# PowerMeasurement.net
KiCad netlist of a schematic drawn in Altium Designer
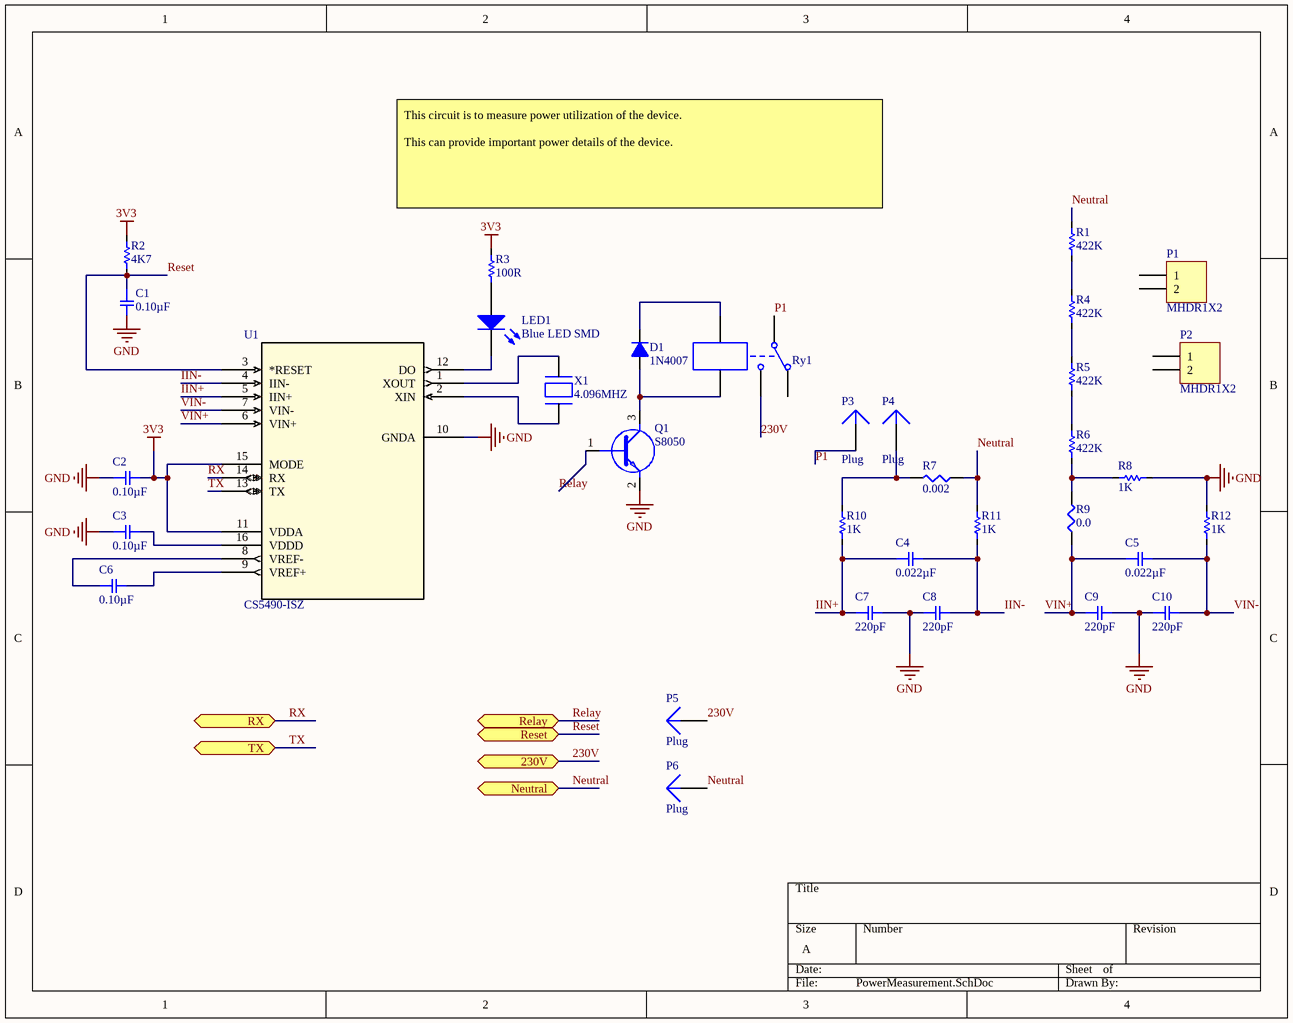
[diagram p0: PowerMeasurement.SchDoc]

(export (version "E")
  (design (tool "Eeschema 10.0.6"))
  (components
    (comp (ref "C1")
      (value "0.10µF")
      (footprint "SMD-0402C")
      (description "CAP CER 0.1UF 16V X7R 0402")
      (fields
        (field (name "DIGI-KEY PART NUMBER") "490-4759-1-ND")
        (field (name "PART NUMBER") "GCM155R71C104KA55D")
      )
      (libsource (lib "Capacitors") (part "GCM155R71C104KA55D"))
    )
    (comp (ref "C2")
      (value "0.10µF")
      (footprint "SMD-0402C")
      (description "CAP CER 0.1UF 16V X7R 0402")
      (fields
        (field (name "DIGI-KEY PART NUMBER") "490-4759-1-ND")
        (field (name "PART NUMBER") "GCM155R71C104KA55D")
      )
      (libsource (lib "Capacitors") (part "GCM155R71C104KA55D"))
    )
    (comp (ref "C3")
      (value "0.10µF")
      (footprint "SMD-0402C")
      (description "CAP CER 0.1UF 16V X7R 0402")
      (fields
        (field (name "DIGI-KEY PART NUMBER") "490-4759-1-ND")
        (field (name "PART NUMBER") "GCM155R71C104KA55D")
      )
      (libsource (lib "Capacitors") (part "GCM155R71C104KA55D"))
    )
    (comp (ref "C4")
      (value "0.022µF")
      (footprint "SMD-0402C")
      (description "CAP CER 0.022UF 50V X7R 0402")
      (fields
        (field (name "DIGI-KEY PART NUMBER") "490-4763-1-ND")
        (field (name "PART NUMBER") "GCM155R71H223KA55D")
      )
      (libsource (lib "Capacitors") (part "GCM155R71H223KA55D"))
    )
    (comp (ref "C5")
      (value "0.022µF")
      (footprint "SMD-0402C")
      (description "CAP CER 0.022UF 50V X7R 0402")
      (fields
        (field (name "DIGI-KEY PART NUMBER") "490-4763-1-ND")
        (field (name "PART NUMBER") "GCM155R71H223KA55D")
      )
      (libsource (lib "Capacitors") (part "GCM155R71H223KA55D"))
    )
    (comp (ref "C6")
      (value "0.10µF")
      (footprint "SMD-0402C")
      (description "CAP CER 0.1UF 16V X7R 0402")
      (fields
        (field (name "DIGI-KEY PART NUMBER") "490-4759-1-ND")
        (field (name "PART NUMBER") "GCM155R71C104KA55D")
      )
      (libsource (lib "Capacitors") (part "GCM155R71C104KA55D"))
    )
    (comp (ref "C7")
      (value "220pF")
      (footprint "SMD-0402C")
      (description "CAP CER 220PF 50V NP0 0402")
      (fields
        (field (name "DIGI-KEY PART NUMBER") "490-4927-1-ND")
        (field (name "PART NUMBER") "GCM1555C1H221JA16D")
      )
      (libsource (lib "Capacitors") (part "GCM1555C1H221JA16D"))
    )
    (comp (ref "C8")
      (value "220pF")
      (footprint "SMD-0402C")
      (description "CAP CER 220PF 50V NP0 0402")
      (fields
        (field (name "DIGI-KEY PART NUMBER") "490-4927-1-ND")
        (field (name "PART NUMBER") "GCM1555C1H221JA16D")
      )
      (libsource (lib "Capacitors") (part "GCM1555C1H221JA16D"))
    )
    (comp (ref "C9")
      (value "220pF")
      (footprint "SMD-0402C")
      (description "CAP CER 220PF 50V NP0 0402")
      (fields
        (field (name "DIGI-KEY PART NUMBER") "490-4927-1-ND")
        (field (name "PART NUMBER") "GCM1555C1H221JA16D")
      )
      (libsource (lib "Capacitors") (part "GCM1555C1H221JA16D"))
    )
    (comp (ref "C10")
      (value "220pF")
      (footprint "SMD-0402C")
      (description "CAP CER 220PF 50V NP0 0402")
      (fields
        (field (name "DIGI-KEY PART NUMBER") "490-4927-1-ND")
        (field (name "PART NUMBER") "GCM1555C1H221JA16D")
      )
      (libsource (lib "Capacitors") (part "GCM1555C1H221JA16D"))
    )
    (comp (ref "D1")
      (value "1N4007")
      (footprint "D2A")
      (description "Diode 1A")
      (libsource (lib "Diodes") (part "1N4007"))
    )
    (comp (ref "LED1")
      (value "Blue LED SMD")
      (footprint "1206 Blue LED SMD")
      (fields (field (name "LATEST REVIEWER") "Zion Blue") (field (name "PUBLISHER") "Cynetik Group"))
      (libsource (lib "Leds_Lib") (part "Blue LED SMD"))
    )
    (comp (ref "P1")
      (value "MHDR1X2")
      (footprint "MHDR1X2")
      (description "Header, 2-Pin")
      (fields (field (name "PUBLISHER") "Altium Limited"))
      (libsource (lib "Miscellaneous Connectors") (part "MHDR1X2"))
    )
    (comp (ref "P2")
      (value "MHDR1X2")
      (footprint "MHDR1X2")
      (description "Header, 2-Pin")
      (fields (field (name "PUBLISHER") "Altium Limited"))
      (libsource (lib "Miscellaneous Connectors") (part "MHDR1X2"))
    )
    (comp (ref "P3")
      (value "Plug")
      (footprint "PIN1")
      (fields (field (name "PUBLISHER") "Altium Limited"))
      (libsource (lib "Miscellaneous Connectors") (part "Plug"))
    )
    (comp (ref "P4")
      (value "Plug")
      (footprint "PIN1")
      (fields (field (name "PUBLISHER") "Altium Limited"))
      (libsource (lib "Miscellaneous Connectors") (part "Plug"))
    )
    (comp (ref "P5")
      (value "Plug")
      (footprint "PIN1")
      (fields (field (name "PUBLISHER") "Altium Limited"))
      (libsource (lib "Miscellaneous Connectors") (part "Plug"))
    )
    (comp (ref "P6")
      (value "Plug")
      (footprint "PIN1")
      (fields (field (name "PUBLISHER") "Altium Limited"))
      (libsource (lib "Miscellaneous Connectors") (part "Plug"))
    )
    (comp (ref "Q1")
      (value "S8050")
      (footprint "SI2305TP")
      (description "TRANS NPN 25V 1.5A SOT23")
      (fields (field (name "MANUFACTURER") "MCC") (field (name "MANUFACTURER PART NUMBER") "MMSS8050-H-TP"))
      (libsource (lib "XBeeLight") (part "MMSS8050-H-TP"))
    )
    (comp (ref "R1")
      (value "422K")
      (footprint "MCS 0402")
      (description "RESISTOR, THICK FILM, 422KOHM, 100mW, ± 1%")
      (fields
        (field (name "MANUFACTURER") "Panasonic")
        (field (name "MANUFACTURER PART NUMBER") "ERJ-2RKF4223X")
      )
      (libsource (lib "XBeeLight") (part "422K"))
    )
    (comp (ref "R2")
      (value "4K7")
      (footprint "MCS 0402")
      (description "Panasonic ERA Series Thin Film Surface Mount Resistor 0402 Case 4.7k 0.1% 0.063W 25ppm/C")
      (fields
        (field (name "MANUFACTURER") "Panasonic")
        (field (name "MANUFACTURER PART NUMBER") "ERA-2AEB472X")
      )
      (libsource (lib "XBeeLight") (part "4K7 Res"))
    )
    (comp (ref "R3")
      (value "100R")
      (footprint "MCS 0402")
      (description "Res Thin Film 0402 100 Ohm 0.5% 0.063W(1/16W) ±25ppm/C Molded SMD Automotive Punched T/R")
      (fields
        (field (name "MANUFACTURER") "Panasonic")
        (field (name "MANUFACTURER PART NUMBER") "ERA-2AED101X")
      )
      (libsource (lib "XBeeLight") (part "100R"))
    )
    (comp (ref "R4")
      (value "422K")
      (footprint "MCS 0402")
      (description "RESISTOR, THICK FILM, 422KOHM, 100mW, ± 1%")
      (fields
        (field (name "MANUFACTURER") "Panasonic")
        (field (name "MANUFACTURER PART NUMBER") "ERJ-2RKF4223X")
      )
      (libsource (lib "XBeeLight") (part "422K"))
    )
    (comp (ref "R5")
      (value "422K")
      (footprint "MCS 0402")
      (description "RESISTOR, THICK FILM, 422KOHM, 100mW, ± 1%")
      (fields
        (field (name "MANUFACTURER") "Panasonic")
        (field (name "MANUFACTURER PART NUMBER") "ERJ-2RKF4223X")
      )
      (libsource (lib "XBeeLight") (part "422K"))
    )
    (comp (ref "R6")
      (value "422K")
      (footprint "MCS 0402")
      (description "RESISTOR, THICK FILM, 422KOHM, 100mW, ± 1%")
      (fields
        (field (name "MANUFACTURER") "Panasonic")
        (field (name "MANUFACTURER PART NUMBER") "ERJ-2RKF4223X")
      )
      (libsource (lib "XBeeLight") (part "422K"))
    )
    (comp (ref "R7")
      (value "0.002")
      (footprint "SMD-2512-RES")
      (description "RES SMD 0.002 OHM 1% 2W 2512")
      (fields
        (field (name "PART NUMBER") "ERJ-MP4PF2M0U")
        (field (name "DIGI-KEY PART NUMBER") "P19407CT-ND")
      )
      (libsource (lib "Panasonic_ERJ_2512") (part "ERJ-MP4PF2M0U"))
    )
    (comp (ref "R8")
      (value "1K")
      (footprint "MCS 0402")
      (description "RES SMD 1K OHM 5% 1/32W 01005")
      (fields
        (field (name "MANUFACTURER") "Panasonic")
        (field (name "MANUFACTURER PART NUMBER") "ERJ-XGNJ102Y")
      )
      (libsource (lib "XBeeLight") (part "1K Res"))
    )
    (comp (ref "R9")
      (value "0.0")
      (footprint "SMD-0402-RES")
      (description "RES SMD 0.0OHM JUMPER 1/10W 0402")
      (fields (field (name "PART NUMBER") "ERJ-2GE0R00X") (field (name "DIGI-KEY PART NUMBER") "P0.0JCT-ND"))
      (libsource (lib "Panasonic_ERJ_0402") (part "ERJ-2GE0R00X"))
    )
    (comp (ref "R10")
      (value "1K")
      (footprint "MCS 0402")
      (description "RES SMD 1K OHM 5% 1/32W 01005")
      (fields
        (field (name "MANUFACTURER") "Panasonic")
        (field (name "MANUFACTURER PART NUMBER") "ERJ-XGNJ102Y")
      )
      (libsource (lib "XBeeLight") (part "1K Res"))
    )
    (comp (ref "R11")
      (value "1K")
      (footprint "MCS 0402")
      (description "RES SMD 1K OHM 5% 1/32W 01005")
      (fields
        (field (name "MANUFACTURER") "Panasonic")
        (field (name "MANUFACTURER PART NUMBER") "ERJ-XGNJ102Y")
      )
      (libsource (lib "XBeeLight") (part "1K Res"))
    )
    (comp (ref "R12")
      (value "1K")
      (footprint "MCS 0402")
      (description "RES SMD 1K OHM 5% 1/32W 01005")
      (fields
        (field (name "MANUFACTURER") "Panasonic")
        (field (name "MANUFACTURER PART NUMBER") "ERJ-XGNJ102Y")
      )
      (libsource (lib "XBeeLight") (part "1K Res"))
    )
    (comp (ref "Ry1")
      (value "Relay")
      (footprint "SRD-05VDC-SL-C")
      (description "Songle Relay")
      (fields (field (name "PUBLISHER") "Cynetik Group") (field (name "LATESTREVIEWER") "Evan Green"))
      (libsource (lib "Relays") (part "SRD-05VDC-SL-C"))
    )
    (comp (ref "U1")
      (value "CS5490-ISZ")
      (footprint "CIR-SOIC-16_W150")
      (description "Imported")
      (libsource (lib "XBeeLight") (part "CS5490-ISZ"))
    )
    (comp (ref "X1")
      (value "4.096MHZ")
      (footprint "XTAL_ABLS2-4.096MHZ-D4Y-T")
      (description "4.096MHz ±30ppm Crystal 18pF 180 Ohm -40°C ~ 85°C  Surface Mount HC49/US")
      (fields
        (field (name "MANUFACTURER") "Abracon")
        (field (name "MANUFACTURER PART NUMBER") "ABLS2-4.096MHZ-D4Y-T")
      )
      (libsource (lib "XBeeLight") (part "ABLS2-4.096MHZ-D4Y-T"))
    )
  )
  (nets
    (net (code "1") (name "/230V") (class "Default")
      (node (ref "P5") (pin "1") (pinfunction "1_1") (pintype "passive"))
      (node (ref "Ry1") (pin "5") (pinfunction "5_5") (pintype "passive"))
    )
    (net (code "2") (name "/IIN+") (class "Default")
      (node (ref "C4") (pin "1") (pinfunction "1_1") (pintype "passive"))
      (node (ref "C7") (pin "1") (pinfunction "1_1") (pintype "passive"))
      (node (ref "R10") (pin "1") (pinfunction "1_1") (pintype "passive"))
      (node (ref "U1") (pin "5") (pinfunction "IIN+_5") (pintype "input"))
    )
    (net (code "3") (name "/IIN-") (class "Default")
      (node (ref "C4") (pin "2") (pinfunction "2_2") (pintype "passive"))
      (node (ref "C8") (pin "2") (pinfunction "2_2") (pintype "passive"))
      (node (ref "R11") (pin "1") (pinfunction "1_1") (pintype "passive"))
      (node (ref "U1") (pin "4") (pinfunction "IIN-_4") (pintype "input"))
    )
    (net (code "4") (name "/Neutral") (class "Default")
      (node (ref "P6") (pin "1") (pinfunction "1_1") (pintype "passive"))
      (node (ref "R1") (pin "2") (pinfunction "2_2") (pintype "passive"))
      (node (ref "R11") (pin "2") (pinfunction "2_2") (pintype "passive"))
      (node (ref "R7") (pin "1") (pinfunction "1_1") (pintype "passive"))
    )
    (net (code "5") (name "/P1") (class "Default")
      (node (ref "P3") (pin "1") (pinfunction "1_1") (pintype "passive"))
      (node (ref "Ry1") (pin "4") (pinfunction "4_4") (pintype "passive"))
    )
    (net (code "6") (name "/RX") (class "Default")
      (node (ref "U1") (pin "14") (pinfunction "RX_14") (pintype "bidirectional"))
    )
    (net (code "7") (name "/Relay") (class "Default")
      (node (ref "Q1") (pin "1") (pinfunction "B_1") (pintype "passive"))
    )
    (net (code "8") (name "/Reset") (class "Default")
      (node (ref "C1") (pin "1") (pinfunction "1_1") (pintype "passive"))
      (node (ref "R2") (pin "1") (pinfunction "1_1") (pintype "passive"))
      (node (ref "U1") (pin "3") (pinfunction "*RESET_3") (pintype "input"))
    )
    (net (code "9") (name "/TX") (class "Default")
      (node (ref "U1") (pin "13") (pinfunction "TX_13") (pintype "bidirectional"))
    )
    (net (code "10") (name "/VIN+") (class "Default")
      (node (ref "C5") (pin "1") (pinfunction "1_1") (pintype "passive"))
      (node (ref "C9") (pin "1") (pinfunction "1_1") (pintype "passive"))
      (node (ref "R9") (pin "1") (pinfunction "1_1") (pintype "passive"))
      (node (ref "U1") (pin "6") (pinfunction "VIN+_6") (pintype "input"))
    )
    (net (code "11") (name "/VIN-") (class "Default")
      (node (ref "C10") (pin "2") (pinfunction "2_2") (pintype "passive"))
      (node (ref "C5") (pin "2") (pinfunction "2_2") (pintype "passive"))
      (node (ref "R12") (pin "1") (pinfunction "1_1") (pintype "passive"))
      (node (ref "U1") (pin "7") (pinfunction "VIN-_7") (pintype "input"))
    )
    (net (code "12") (name "3V3") (class "Default")
      (node (ref "C2") (pin "2") (pinfunction "2_2") (pintype "passive"))
      (node (ref "R2") (pin "2") (pinfunction "2_2") (pintype "passive"))
      (node (ref "R3") (pin "2") (pinfunction "2_2") (pintype "passive"))
      (node (ref "U1") (pin "11") (pinfunction "VDDA_11") (pintype "power_in"))
      (node (ref "U1") (pin "15") (pinfunction "MODE_15") (pintype "passive"))
    )
    (net (code "13") (name "GND") (class "Default")
      (node (ref "C1") (pin "2") (pinfunction "2_2") (pintype "passive"))
      (node (ref "C10") (pin "1") (pinfunction "1_1") (pintype "passive"))
      (node (ref "C2") (pin "1") (pinfunction "1_1") (pintype "passive"))
      (node (ref "C3") (pin "1") (pinfunction "1_1") (pintype "passive"))
      (node (ref "C7") (pin "2") (pinfunction "2_2") (pintype "passive"))
      (node (ref "C8") (pin "1") (pinfunction "1_1") (pintype "passive"))
      (node (ref "C9") (pin "2") (pinfunction "2_2") (pintype "passive"))
      (node (ref "Q1") (pin "2") (pinfunction "E_2") (pintype "passive"))
      (node (ref "R12") (pin "2") (pinfunction "2_2") (pintype "passive"))
      (node (ref "R8") (pin "1") (pinfunction "1_1") (pintype "passive"))
      (node (ref "U1") (pin "10") (pinfunction "GNDA_10") (pintype "power_in"))
    )
    (net (code "14") (name "Net-(D1-A)") (class "Default")
      (node (ref "D1") (pin "1") (pinfunction "A_1") (pintype "passive"))
      (node (ref "Q1") (pin "3") (pinfunction "C_3") (pintype "passive"))
      (node (ref "Ry1") (pin "2") (pinfunction "2_2") (pintype "passive"))
    )
    (net (code "15") (name "Net-(D1-K)") (class "Default")
      (node (ref "D1") (pin "2") (pinfunction "K_2") (pintype "passive"))
      (node (ref "Ry1") (pin "1") (pinfunction "1_1") (pintype "passive"))
    )
    (net (code "16") (name "Net-(LED1-A)") (class "Default")
      (node (ref "LED1") (pin "1") (pinfunction "A_1") (pintype "passive"))
      (node (ref "R3") (pin "1") (pinfunction "1_1") (pintype "passive"))
    )
    (net (code "17") (name "Net-(LED1-K)") (class "Default")
      (node (ref "LED1") (pin "2") (pinfunction "K_2") (pintype "passive"))
      (node (ref "U1") (pin "12") (pinfunction "DO_12") (pintype "output"))
    )
    (net (code "18") (name "Net-(P4-Pad1)") (class "Default")
      (node (ref "P4") (pin "1") (pinfunction "1_1") (pintype "passive"))
      (node (ref "R10") (pin "2") (pinfunction "2_2") (pintype "passive"))
      (node (ref "R7") (pin "2") (pinfunction "2_2") (pintype "passive"))
    )
    (net (code "19") (name "Net-(R1-Pad1)") (class "Default")
      (node (ref "R1") (pin "1") (pinfunction "1_1") (pintype "passive"))
      (node (ref "R4") (pin "2") (pinfunction "2_2") (pintype "passive"))
    )
    (net (code "20") (name "Net-(R4-Pad1)") (class "Default")
      (node (ref "R4") (pin "1") (pinfunction "1_1") (pintype "passive"))
      (node (ref "R5") (pin "2") (pinfunction "2_2") (pintype "passive"))
    )
    (net (code "21") (name "Net-(R5-Pad1)") (class "Default")
      (node (ref "R5") (pin "1") (pinfunction "1_1") (pintype "passive"))
      (node (ref "R6") (pin "2") (pinfunction "2_2") (pintype "passive"))
    )
    (net (code "22") (name "Net-(R6-Pad1)") (class "Default")
      (node (ref "R6") (pin "1") (pinfunction "1_1") (pintype "passive"))
      (node (ref "R8") (pin "2") (pinfunction "2_2") (pintype "passive"))
      (node (ref "R9") (pin "2") (pinfunction "2_2") (pintype "passive"))
    )
    (net (code "23") (name "Net-(U1-VDDD)") (class "Default")
      (node (ref "C3") (pin "2") (pinfunction "2_2") (pintype "passive"))
      (node (ref "U1") (pin "16") (pinfunction "VDDD_16") (pintype "power_in"))
    )
    (net (code "24") (name "Net-(U1-VREF+)") (class "Default")
      (node (ref "C6") (pin "2") (pinfunction "2_2") (pintype "passive"))
      (node (ref "U1") (pin "9") (pinfunction "VREF+_9") (pintype "output"))
    )
    (net (code "25") (name "Net-(U1-VREF-)") (class "Default")
      (node (ref "C6") (pin "1") (pinfunction "1_1") (pintype "passive"))
      (node (ref "U1") (pin "8") (pinfunction "VREF-_8") (pintype "output"))
    )
    (net (code "26") (name "Net-(U1-XIN)") (class "Default")
      (node (ref "U1") (pin "2") (pinfunction "XIN_2") (pintype "input"))
      (node (ref "X1") (pin "1") (pinfunction "1_1") (pintype "passive"))
    )
    (net (code "27") (name "Net-(U1-XOUT)") (class "Default")
      (node (ref "U1") (pin "1") (pinfunction "XOUT_1") (pintype "output"))
      (node (ref "X1") (pin "2") (pinfunction "2_2") (pintype "passive"))
    )
    (net (code "28") (name "unconnected-(P1-Pad1)") (class "Default")
      (node (ref "P1") (pin "1") (pinfunction "1_1") (pintype "passive"))
    )
    (net (code "29") (name "unconnected-(P1-Pad2)") (class "Default")
      (node (ref "P1") (pin "2") (pinfunction "2_2") (pintype "passive"))
    )
    (net (code "30") (name "unconnected-(P2-Pad1)") (class "Default")
      (node (ref "P2") (pin "1") (pinfunction "1_1") (pintype "passive"))
    )
    (net (code "31") (name "unconnected-(P2-Pad2)") (class "Default")
      (node (ref "P2") (pin "2") (pinfunction "2_2") (pintype "passive"))
    )
    (net (code "32") (name "unconnected-(Ry1-Pad3)") (class "Default")
      (node (ref "Ry1") (pin "3") (pinfunction "3_3") (pintype "passive"))
    )
  )
)
